# Switch_External.net
KiCad netlist of a schematic drawn in Altium Designer
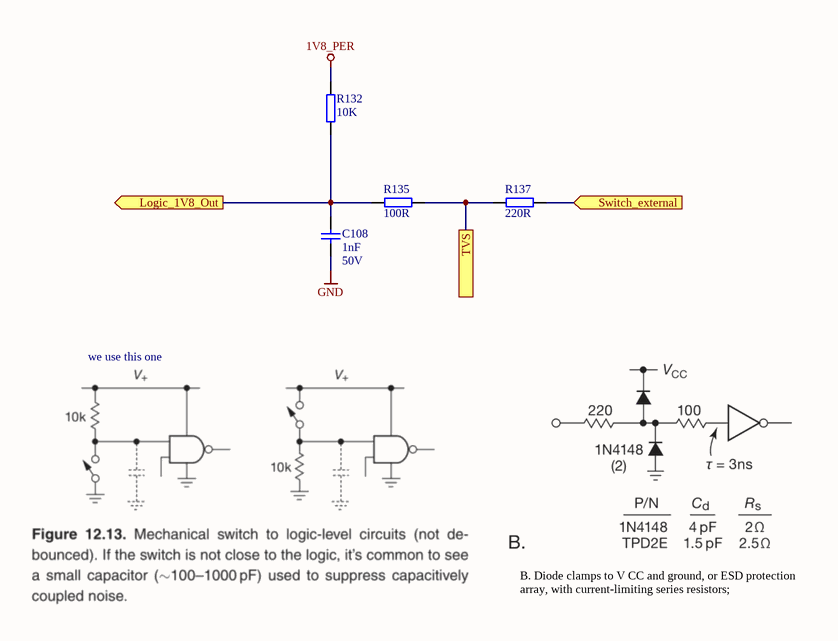
[diagram p0: Switch_External.SchDoc]

(export (version "E")
  (design (tool "Eeschema 10.0.6"))
  (components
    (comp (ref "C108")
      (value "1nF")
      (footprint "CAPC1608X90N_V")
      (description "KON 1nF 50V NP0 5% SMD BF 1608 (0603)")
      (fields (field (name "VOLTAGE") "50V"))
      (libsource (lib "TE") (part "CAP-NP"))
    )
    (comp (ref "R132")
      (value "10K")
      (footprint "RESC1608X55N_V")
      (description "WID SMD 10K 1% 0,1W  BF 1608 (0603)")
      (fields (field (name "TOLERANCE") "1%"))
      (libsource (lib "TE") (part "RES"))
    )
    (comp (ref "R135")
      (value "100R")
      (footprint "RESC1608X55N_V")
      (description "WID SMD 100R 1% 0,1W BF 1608 (0603)")
      (fields (field (name "TOLERANCE") "1%"))
      (libsource (lib "TE") (part "RES"))
    )
    (comp (ref "R137")
      (value "220R")
      (footprint "RESC1608X55N_V")
      (description "WID SMD 220R 1% 0,1W")
      (fields (field (name "TOLERANCE") "1%"))
      (libsource (lib "TE") (part "RES"))
    )
  )
  (nets
    (net (code "1") (name "/Logic_1V8_Out") (class "Default")
      (node (ref "C108") (pin "2") (pinfunction "2_2") (pintype "passive"))
      (node (ref "R132") (pin "1") (pinfunction "1_1") (pintype "passive"))
      (node (ref "R135") (pin "1") (pinfunction "1_1") (pintype "passive"))
    )
    (net (code "2") (name "/Switch_external") (class "Default")
      (node (ref "R137") (pin "1") (pinfunction "1_1") (pintype "passive"))
    )
    (net (code "3") (name "/TVS") (class "Default")
      (node (ref "R135") (pin "2") (pinfunction "2_2") (pintype "passive"))
      (node (ref "R137") (pin "2") (pinfunction "2_2") (pintype "passive"))
    )
    (net (code "4") (name "1V8_PER") (class "Default")
      (node (ref "R132") (pin "2") (pinfunction "2_2") (pintype "passive"))
    )
    (net (code "5") (name "GND") (class "Default")
      (node (ref "C108") (pin "1") (pinfunction "1_1") (pintype "passive"))
    )
  )
)
